# CBLine.net
KiCad netlist of a schematic drawn in Altium Designer
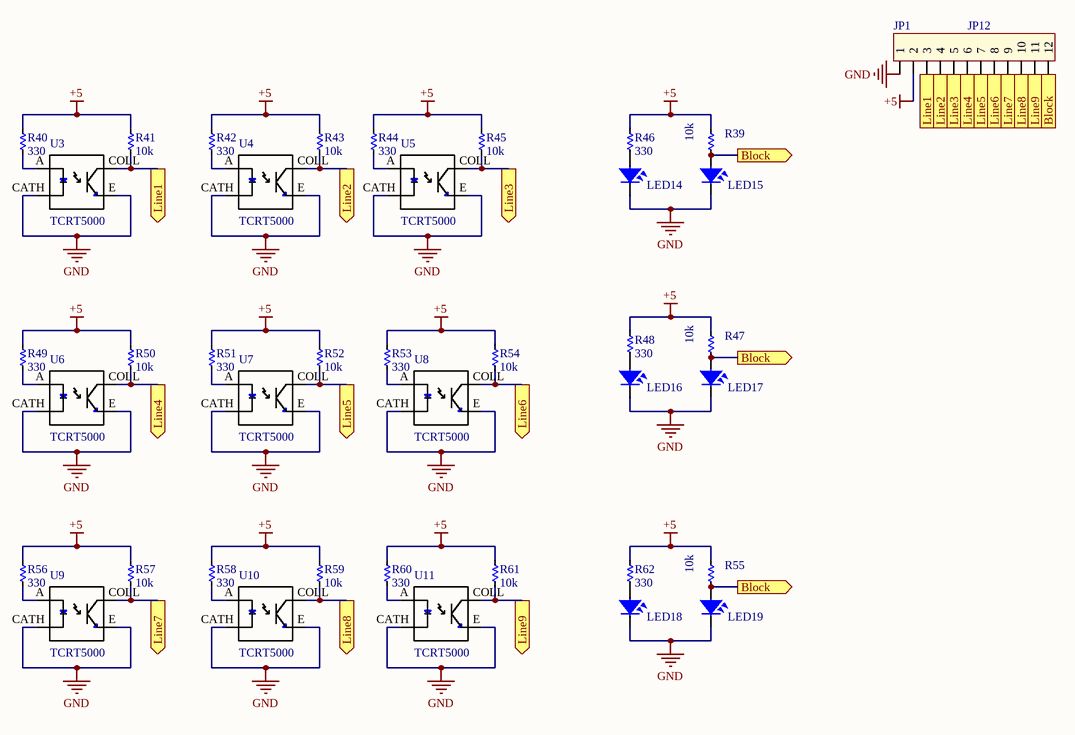
[diagram p0: CBLine.SchDoc]

(export (version "E")
  (design (tool "Eeschema 10.0.6"))
  (components
    (comp (ref "JP1")
      (value "JP12")
      (footprint "Header12")
      (description "Connector 12")
      (libsource (lib "Thư Viện Altium FULL HD") (part "Header12"))
    )
    (comp (ref "LED14")
      (value "LED")
      (footprint "LED-3MM-YELLOW")
      (description "LED Single colour Green and Red")
      (libsource (lib "Thư Viện Altium FULL HD") (part "LED"))
    )
    (comp (ref "LED15")
      (value "LED")
      (footprint "LED-3MM-YELLOW")
      (description "LED Single colour Green and Red")
      (libsource (lib "Thư Viện Altium FULL HD") (part "LED"))
    )
    (comp (ref "LED16")
      (value "LED")
      (footprint "LED-3MM-YELLOW")
      (description "LED Single colour Green and Red")
      (libsource (lib "Thư Viện Altium FULL HD") (part "LED"))
    )
    (comp (ref "LED17")
      (value "LED")
      (footprint "LED-3MM-YELLOW")
      (description "LED Single colour Green and Red")
      (libsource (lib "Thư Viện Altium FULL HD") (part "LED"))
    )
    (comp (ref "LED18")
      (value "LED")
      (footprint "LED-3MM-YELLOW")
      (description "LED Single colour Green and Red")
      (libsource (lib "Thư Viện Altium FULL HD") (part "LED"))
    )
    (comp (ref "LED19")
      (value "LED")
      (footprint "LED-3MM-YELLOW")
      (description "LED Single colour Green and Red")
      (libsource (lib "Thư Viện Altium FULL HD") (part "LED"))
    )
    (comp (ref "R39")
      (value "10k")
      (footprint "RES-SMD-0805")
      (description "Resistor")
      (fields
        (field (name "MANUFACTURER") "Generic Components")
        (field (name "PUBLISHER") "Altium Hobart Technology Centre")
      )
      (libsource (lib "Thư Viện Altium FULL HD") (part "Res-SMD"))
    )
    (comp (ref "R40")
      (value "330")
      (footprint "RES-SMD-0805")
      (description "Resistor")
      (fields
        (field (name "MANUFACTURER") "Generic Components")
        (field (name "PUBLISHER") "Altium Hobart Technology Centre")
      )
      (libsource (lib "Thư Viện Altium FULL HD") (part "Res-SMD"))
    )
    (comp (ref "R41")
      (value "10k")
      (footprint "RES-SMD-0805")
      (description "Resistor")
      (fields
        (field (name "MANUFACTURER") "Generic Components")
        (field (name "PUBLISHER") "Altium Hobart Technology Centre")
      )
      (libsource (lib "Thư Viện Altium FULL HD") (part "Res-SMD"))
    )
    (comp (ref "R42")
      (value "330")
      (footprint "RES-SMD-0805")
      (description "Resistor")
      (fields
        (field (name "MANUFACTURER") "Generic Components")
        (field (name "PUBLISHER") "Altium Hobart Technology Centre")
      )
      (libsource (lib "Thư Viện Altium FULL HD") (part "Res-SMD"))
    )
    (comp (ref "R43")
      (value "10k")
      (footprint "RES-SMD-0805")
      (description "Resistor")
      (fields
        (field (name "MANUFACTURER") "Generic Components")
        (field (name "PUBLISHER") "Altium Hobart Technology Centre")
      )
      (libsource (lib "Thư Viện Altium FULL HD") (part "Res-SMD"))
    )
    (comp (ref "R44")
      (value "330")
      (footprint "RES-SMD-0805")
      (description "Resistor")
      (fields
        (field (name "MANUFACTURER") "Generic Components")
        (field (name "PUBLISHER") "Altium Hobart Technology Centre")
      )
      (libsource (lib "Thư Viện Altium FULL HD") (part "Res-SMD"))
    )
    (comp (ref "R45")
      (value "10k")
      (footprint "RES-SMD-0805")
      (description "Resistor")
      (fields
        (field (name "MANUFACTURER") "Generic Components")
        (field (name "PUBLISHER") "Altium Hobart Technology Centre")
      )
      (libsource (lib "Thư Viện Altium FULL HD") (part "Res-SMD"))
    )
    (comp (ref "R46")
      (value "330")
      (footprint "RES-SMD-0805")
      (description "Resistor")
      (fields
        (field (name "MANUFACTURER") "Generic Components")
        (field (name "PUBLISHER") "Altium Hobart Technology Centre")
      )
      (libsource (lib "Thư Viện Altium FULL HD") (part "Res-SMD"))
    )
    (comp (ref "R47")
      (value "10k")
      (footprint "RES-SMD-0805")
      (description "Resistor")
      (fields
        (field (name "MANUFACTURER") "Generic Components")
        (field (name "PUBLISHER") "Altium Hobart Technology Centre")
      )
      (libsource (lib "Thư Viện Altium FULL HD") (part "Res-SMD"))
    )
    (comp (ref "R48")
      (value "330")
      (footprint "RES-SMD-0805")
      (description "Resistor")
      (fields
        (field (name "MANUFACTURER") "Generic Components")
        (field (name "PUBLISHER") "Altium Hobart Technology Centre")
      )
      (libsource (lib "Thư Viện Altium FULL HD") (part "Res-SMD"))
    )
    (comp (ref "R49")
      (value "330")
      (footprint "RES-SMD-0805")
      (description "Resistor")
      (fields
        (field (name "MANUFACTURER") "Generic Components")
        (field (name "PUBLISHER") "Altium Hobart Technology Centre")
      )
      (libsource (lib "Thư Viện Altium FULL HD") (part "Res-SMD"))
    )
    (comp (ref "R50")
      (value "10k")
      (footprint "RES-SMD-0805")
      (description "Resistor")
      (fields
        (field (name "MANUFACTURER") "Generic Components")
        (field (name "PUBLISHER") "Altium Hobart Technology Centre")
      )
      (libsource (lib "Thư Viện Altium FULL HD") (part "Res-SMD"))
    )
    (comp (ref "R51")
      (value "330")
      (footprint "RES-SMD-0805")
      (description "Resistor")
      (fields
        (field (name "MANUFACTURER") "Generic Components")
        (field (name "PUBLISHER") "Altium Hobart Technology Centre")
      )
      (libsource (lib "Thư Viện Altium FULL HD") (part "Res-SMD"))
    )
    (comp (ref "R52")
      (value "10k")
      (footprint "RES-SMD-0805")
      (description "Resistor")
      (fields
        (field (name "MANUFACTURER") "Generic Components")
        (field (name "PUBLISHER") "Altium Hobart Technology Centre")
      )
      (libsource (lib "Thư Viện Altium FULL HD") (part "Res-SMD"))
    )
    (comp (ref "R53")
      (value "330")
      (footprint "RES-SMD-0805")
      (description "Resistor")
      (fields
        (field (name "MANUFACTURER") "Generic Components")
        (field (name "PUBLISHER") "Altium Hobart Technology Centre")
      )
      (libsource (lib "Thư Viện Altium FULL HD") (part "Res-SMD"))
    )
    (comp (ref "R54")
      (value "10k")
      (footprint "RES-SMD-0805")
      (description "Resistor")
      (fields
        (field (name "MANUFACTURER") "Generic Components")
        (field (name "PUBLISHER") "Altium Hobart Technology Centre")
      )
      (libsource (lib "Thư Viện Altium FULL HD") (part "Res-SMD"))
    )
    (comp (ref "R55")
      (value "10k")
      (footprint "RES-SMD-0805")
      (description "Resistor")
      (fields
        (field (name "MANUFACTURER") "Generic Components")
        (field (name "PUBLISHER") "Altium Hobart Technology Centre")
      )
      (libsource (lib "Thư Viện Altium FULL HD") (part "Res-SMD"))
    )
    (comp (ref "R56")
      (value "330")
      (footprint "RES-SMD-0805")
      (description "Resistor")
      (fields
        (field (name "MANUFACTURER") "Generic Components")
        (field (name "PUBLISHER") "Altium Hobart Technology Centre")
      )
      (libsource (lib "Thư Viện Altium FULL HD") (part "Res-SMD"))
    )
    (comp (ref "R57")
      (value "10k")
      (footprint "RES-SMD-0805")
      (description "Resistor")
      (fields
        (field (name "MANUFACTURER") "Generic Components")
        (field (name "PUBLISHER") "Altium Hobart Technology Centre")
      )
      (libsource (lib "Thư Viện Altium FULL HD") (part "Res-SMD"))
    )
    (comp (ref "R58")
      (value "330")
      (footprint "RES-SMD-0805")
      (description "Resistor")
      (fields
        (field (name "MANUFACTURER") "Generic Components")
        (field (name "PUBLISHER") "Altium Hobart Technology Centre")
      )
      (libsource (lib "Thư Viện Altium FULL HD") (part "Res-SMD"))
    )
    (comp (ref "R59")
      (value "10k")
      (footprint "RES-SMD-0805")
      (description "Resistor")
      (fields
        (field (name "MANUFACTURER") "Generic Components")
        (field (name "PUBLISHER") "Altium Hobart Technology Centre")
      )
      (libsource (lib "Thư Viện Altium FULL HD") (part "Res-SMD"))
    )
    (comp (ref "R60")
      (value "330")
      (footprint "RES-SMD-0805")
      (description "Resistor")
      (fields
        (field (name "MANUFACTURER") "Generic Components")
        (field (name "PUBLISHER") "Altium Hobart Technology Centre")
      )
      (libsource (lib "Thư Viện Altium FULL HD") (part "Res-SMD"))
    )
    (comp (ref "R61")
      (value "10k")
      (footprint "RES-SMD-0805")
      (description "Resistor")
      (fields
        (field (name "MANUFACTURER") "Generic Components")
        (field (name "PUBLISHER") "Altium Hobart Technology Centre")
      )
      (libsource (lib "Thư Viện Altium FULL HD") (part "Res-SMD"))
    )
    (comp (ref "R62")
      (value "330")
      (footprint "RES-SMD-0805")
      (description "Resistor")
      (fields
        (field (name "MANUFACTURER") "Generic Components")
        (field (name "PUBLISHER") "Altium Hobart Technology Centre")
      )
      (libsource (lib "Thư Viện Altium FULL HD") (part "Res-SMD"))
    )
    (comp (ref "U3")
      (value "TCRT5000")
      (footprint "*OPTO_TCRT5000_TCRT5000(Primary)")
      (description "950 nm 60 mA Through Hole Reflective Optical Sensor with Transistor Output")
      (fields (field (name "MF") "Vishay"))
      (libsource (lib "TCRT5000") (part "TCRT5000"))
    )
    (comp (ref "U4")
      (value "TCRT5000")
      (footprint "*OPTO_TCRT5000_TCRT5000(Primary)")
      (description "950 nm 60 mA Through Hole Reflective Optical Sensor with Transistor Output")
      (fields (field (name "MF") "Vishay"))
      (libsource (lib "TCRT5000") (part "TCRT5000"))
    )
    (comp (ref "U5")
      (value "TCRT5000")
      (footprint "*OPTO_TCRT5000_TCRT5000(Primary)")
      (description "950 nm 60 mA Through Hole Reflective Optical Sensor with Transistor Output")
      (fields (field (name "MF") "Vishay"))
      (libsource (lib "TCRT5000") (part "TCRT5000"))
    )
    (comp (ref "U6")
      (value "TCRT5000")
      (footprint "*OPTO_TCRT5000_TCRT5000(Primary)")
      (description "950 nm 60 mA Through Hole Reflective Optical Sensor with Transistor Output")
      (fields (field (name "MF") "Vishay"))
      (libsource (lib "TCRT5000") (part "TCRT5000"))
    )
    (comp (ref "U7")
      (value "TCRT5000")
      (footprint "*OPTO_TCRT5000_TCRT5000(Primary)")
      (description "950 nm 60 mA Through Hole Reflective Optical Sensor with Transistor Output")
      (fields (field (name "MF") "Vishay"))
      (libsource (lib "TCRT5000") (part "TCRT5000"))
    )
    (comp (ref "U8")
      (value "TCRT5000")
      (footprint "*OPTO_TCRT5000_TCRT5000(Primary)")
      (description "950 nm 60 mA Through Hole Reflective Optical Sensor with Transistor Output")
      (fields (field (name "MF") "Vishay"))
      (libsource (lib "TCRT5000") (part "TCRT5000"))
    )
    (comp (ref "U9")
      (value "TCRT5000")
      (footprint "*OPTO_TCRT5000_TCRT5000(Primary)")
      (description "950 nm 60 mA Through Hole Reflective Optical Sensor with Transistor Output")
      (fields (field (name "MF") "Vishay"))
      (libsource (lib "TCRT5000") (part "TCRT5000"))
    )
    (comp (ref "U10")
      (value "TCRT5000")
      (footprint "*OPTO_TCRT5000_TCRT5000(Primary)")
      (description "950 nm 60 mA Through Hole Reflective Optical Sensor with Transistor Output")
      (fields (field (name "MF") "Vishay"))
      (libsource (lib "TCRT5000") (part "TCRT5000"))
    )
    (comp (ref "U11")
      (value "TCRT5000")
      (footprint "*OPTO_TCRT5000_TCRT5000(Primary)")
      (description "950 nm 60 mA Through Hole Reflective Optical Sensor with Transistor Output")
      (fields (field (name "MF") "Vishay"))
      (libsource (lib "TCRT5000") (part "TCRT5000"))
    )
  )
  (nets
    (net (code "1") (name "+5") (class "Default")
      (node (ref "JP1") (pin "2") (pinfunction "2_2") (pintype "passive"))
      (node (ref "R39") (pin "1") (pinfunction "1_1") (pintype "passive"))
      (node (ref "R40") (pin "1") (pinfunction "1_1") (pintype "passive"))
      (node (ref "R41") (pin "1") (pinfunction "1_1") (pintype "passive"))
      (node (ref "R42") (pin "1") (pinfunction "1_1") (pintype "passive"))
      (node (ref "R43") (pin "1") (pinfunction "1_1") (pintype "passive"))
      (node (ref "R44") (pin "1") (pinfunction "1_1") (pintype "passive"))
      (node (ref "R45") (pin "1") (pinfunction "1_1") (pintype "passive"))
      (node (ref "R46") (pin "1") (pinfunction "1_1") (pintype "passive"))
      (node (ref "R47") (pin "1") (pinfunction "1_1") (pintype "passive"))
      (node (ref "R48") (pin "1") (pinfunction "1_1") (pintype "passive"))
      (node (ref "R49") (pin "1") (pinfunction "1_1") (pintype "passive"))
      (node (ref "R50") (pin "1") (pinfunction "1_1") (pintype "passive"))
      (node (ref "R51") (pin "1") (pinfunction "1_1") (pintype "passive"))
      (node (ref "R52") (pin "1") (pinfunction "1_1") (pintype "passive"))
      (node (ref "R53") (pin "1") (pinfunction "1_1") (pintype "passive"))
      (node (ref "R54") (pin "1") (pinfunction "1_1") (pintype "passive"))
      (node (ref "R55") (pin "1") (pinfunction "1_1") (pintype "passive"))
      (node (ref "R56") (pin "1") (pinfunction "1_1") (pintype "passive"))
      (node (ref "R57") (pin "1") (pinfunction "1_1") (pintype "passive"))
      (node (ref "R58") (pin "1") (pinfunction "1_1") (pintype "passive"))
      (node (ref "R59") (pin "1") (pinfunction "1_1") (pintype "passive"))
      (node (ref "R60") (pin "1") (pinfunction "1_1") (pintype "passive"))
      (node (ref "R61") (pin "1") (pinfunction "1_1") (pintype "passive"))
      (node (ref "R62") (pin "1") (pinfunction "1_1") (pintype "passive"))
    )
    (net (code "2") (name "/Block") (class "Default")
      (node (ref "JP1") (pin "12") (pinfunction "12_12") (pintype "passive"))
      (node (ref "LED15") (pin "1") (pinfunction "1_1") (pintype "passive"))
      (node (ref "LED17") (pin "1") (pinfunction "1_1") (pintype "passive"))
      (node (ref "LED19") (pin "1") (pinfunction "1_1") (pintype "passive"))
      (node (ref "R39") (pin "2") (pinfunction "2_2") (pintype "passive"))
      (node (ref "R47") (pin "2") (pinfunction "2_2") (pintype "passive"))
      (node (ref "R55") (pin "2") (pinfunction "2_2") (pintype "passive"))
    )
    (net (code "3") (name "/Line1") (class "Default")
      (node (ref "JP1") (pin "3") (pinfunction "3_3") (pintype "passive"))
      (node (ref "R41") (pin "2") (pinfunction "2_2") (pintype "passive"))
      (node (ref "U3") (pin "COLL") (pinfunction "COLL_COLL") (pintype "passive"))
    )
    (net (code "4") (name "/Line2") (class "Default")
      (node (ref "JP1") (pin "4") (pinfunction "4_4") (pintype "passive"))
      (node (ref "R43") (pin "2") (pinfunction "2_2") (pintype "passive"))
      (node (ref "U4") (pin "COLL") (pinfunction "COLL_COLL") (pintype "passive"))
    )
    (net (code "5") (name "/Line3") (class "Default")
      (node (ref "JP1") (pin "5") (pinfunction "5_5") (pintype "passive"))
      (node (ref "R45") (pin "2") (pinfunction "2_2") (pintype "passive"))
      (node (ref "U5") (pin "COLL") (pinfunction "COLL_COLL") (pintype "passive"))
    )
    (net (code "6") (name "/Line4") (class "Default")
      (node (ref "JP1") (pin "6") (pinfunction "6_6") (pintype "passive"))
      (node (ref "R50") (pin "2") (pinfunction "2_2") (pintype "passive"))
      (node (ref "U6") (pin "COLL") (pinfunction "COLL_COLL") (pintype "passive"))
    )
    (net (code "7") (name "/Line5") (class "Default")
      (node (ref "JP1") (pin "7") (pinfunction "7_7") (pintype "passive"))
      (node (ref "R52") (pin "2") (pinfunction "2_2") (pintype "passive"))
      (node (ref "U7") (pin "COLL") (pinfunction "COLL_COLL") (pintype "passive"))
    )
    (net (code "8") (name "/Line6") (class "Default")
      (node (ref "JP1") (pin "8") (pinfunction "8_8") (pintype "passive"))
      (node (ref "R54") (pin "2") (pinfunction "2_2") (pintype "passive"))
      (node (ref "U8") (pin "COLL") (pinfunction "COLL_COLL") (pintype "passive"))
    )
    (net (code "9") (name "/Line7") (class "Default")
      (node (ref "JP1") (pin "9") (pinfunction "9_9") (pintype "passive"))
      (node (ref "R57") (pin "2") (pinfunction "2_2") (pintype "passive"))
      (node (ref "U9") (pin "COLL") (pinfunction "COLL_COLL") (pintype "passive"))
    )
    (net (code "10") (name "/Line8") (class "Default")
      (node (ref "JP1") (pin "10") (pinfunction "10_10") (pintype "passive"))
      (node (ref "R59") (pin "2") (pinfunction "2_2") (pintype "passive"))
      (node (ref "U10") (pin "COLL") (pinfunction "COLL_COLL") (pintype "passive"))
    )
    (net (code "11") (name "/Line9") (class "Default")
      (node (ref "JP1") (pin "11") (pinfunction "11_11") (pintype "passive"))
      (node (ref "R61") (pin "2") (pinfunction "2_2") (pintype "passive"))
      (node (ref "U11") (pin "COLL") (pinfunction "COLL_COLL") (pintype "passive"))
    )
    (net (code "12") (name "GND") (class "Default")
      (node (ref "JP1") (pin "1") (pinfunction "1_1") (pintype "passive"))
      (node (ref "LED14") (pin "2") (pinfunction "2_2") (pintype "passive"))
      (node (ref "LED15") (pin "2") (pinfunction "2_2") (pintype "passive"))
      (node (ref "LED16") (pin "2") (pinfunction "2_2") (pintype "passive"))
      (node (ref "LED17") (pin "2") (pinfunction "2_2") (pintype "passive"))
      (node (ref "LED18") (pin "2") (pinfunction "2_2") (pintype "passive"))
      (node (ref "LED19") (pin "2") (pinfunction "2_2") (pintype "passive"))
      (node (ref "U10") (pin "CATH") (pinfunction "CATH_CATH") (pintype "passive"))
      (node (ref "U10") (pin "E") (pinfunction "E_E") (pintype "passive"))
      (node (ref "U11") (pin "CATH") (pinfunction "CATH_CATH") (pintype "passive"))
      (node (ref "U11") (pin "E") (pinfunction "E_E") (pintype "passive"))
      (node (ref "U3") (pin "CATH") (pinfunction "CATH_CATH") (pintype "passive"))
      (node (ref "U3") (pin "E") (pinfunction "E_E") (pintype "passive"))
      (node (ref "U4") (pin "CATH") (pinfunction "CATH_CATH") (pintype "passive"))
      (node (ref "U4") (pin "E") (pinfunction "E_E") (pintype "passive"))
      (node (ref "U5") (pin "CATH") (pinfunction "CATH_CATH") (pintype "passive"))
      (node (ref "U5") (pin "E") (pinfunction "E_E") (pintype "passive"))
      (node (ref "U6") (pin "CATH") (pinfunction "CATH_CATH") (pintype "passive"))
      (node (ref "U6") (pin "E") (pinfunction "E_E") (pintype "passive"))
      (node (ref "U7") (pin "CATH") (pinfunction "CATH_CATH") (pintype "passive"))
      (node (ref "U7") (pin "E") (pinfunction "E_E") (pintype "passive"))
      (node (ref "U8") (pin "CATH") (pinfunction "CATH_CATH") (pintype "passive"))
      (node (ref "U8") (pin "E") (pinfunction "E_E") (pintype "passive"))
      (node (ref "U9") (pin "CATH") (pinfunction "CATH_CATH") (pintype "passive"))
      (node (ref "U9") (pin "E") (pinfunction "E_E") (pintype "passive"))
    )
    (net (code "13") (name "Net-(LED14-Pad1)") (class "Default")
      (node (ref "LED14") (pin "1") (pinfunction "1_1") (pintype "passive"))
      (node (ref "R46") (pin "2") (pinfunction "2_2") (pintype "passive"))
    )
    (net (code "14") (name "Net-(LED16-Pad1)") (class "Default")
      (node (ref "LED16") (pin "1") (pinfunction "1_1") (pintype "passive"))
      (node (ref "R48") (pin "2") (pinfunction "2_2") (pintype "passive"))
    )
    (net (code "15") (name "Net-(LED18-Pad1)") (class "Default")
      (node (ref "LED18") (pin "1") (pinfunction "1_1") (pintype "passive"))
      (node (ref "R62") (pin "2") (pinfunction "2_2") (pintype "passive"))
    )
    (net (code "16") (name "Net-(R40-Pad2)") (class "Default")
      (node (ref "R40") (pin "2") (pinfunction "2_2") (pintype "passive"))
      (node (ref "U3") (pin "A") (pinfunction "A_A") (pintype "passive"))
    )
    (net (code "17") (name "Net-(R42-Pad2)") (class "Default")
      (node (ref "R42") (pin "2") (pinfunction "2_2") (pintype "passive"))
      (node (ref "U4") (pin "A") (pinfunction "A_A") (pintype "passive"))
    )
    (net (code "18") (name "Net-(R44-Pad2)") (class "Default")
      (node (ref "R44") (pin "2") (pinfunction "2_2") (pintype "passive"))
      (node (ref "U5") (pin "A") (pinfunction "A_A") (pintype "passive"))
    )
    (net (code "19") (name "Net-(R49-Pad2)") (class "Default")
      (node (ref "R49") (pin "2") (pinfunction "2_2") (pintype "passive"))
      (node (ref "U6") (pin "A") (pinfunction "A_A") (pintype "passive"))
    )
    (net (code "20") (name "Net-(R51-Pad2)") (class "Default")
      (node (ref "R51") (pin "2") (pinfunction "2_2") (pintype "passive"))
      (node (ref "U7") (pin "A") (pinfunction "A_A") (pintype "passive"))
    )
    (net (code "21") (name "Net-(R53-Pad2)") (class "Default")
      (node (ref "R53") (pin "2") (pinfunction "2_2") (pintype "passive"))
      (node (ref "U8") (pin "A") (pinfunction "A_A") (pintype "passive"))
    )
    (net (code "22") (name "Net-(R56-Pad2)") (class "Default")
      (node (ref "R56") (pin "2") (pinfunction "2_2") (pintype "passive"))
      (node (ref "U9") (pin "A") (pinfunction "A_A") (pintype "passive"))
    )
    (net (code "23") (name "Net-(R58-Pad2)") (class "Default")
      (node (ref "R58") (pin "2") (pinfunction "2_2") (pintype "passive"))
      (node (ref "U10") (pin "A") (pinfunction "A_A") (pintype "passive"))
    )
    (net (code "24") (name "Net-(R60-Pad2)") (class "Default")
      (node (ref "R60") (pin "2") (pinfunction "2_2") (pintype "passive"))
      (node (ref "U11") (pin "A") (pinfunction "A_A") (pintype "passive"))
    )
  )
)
